# Diff-Probe-Supply.net
KiCad netlist of a schematic drawn in Altium Designer
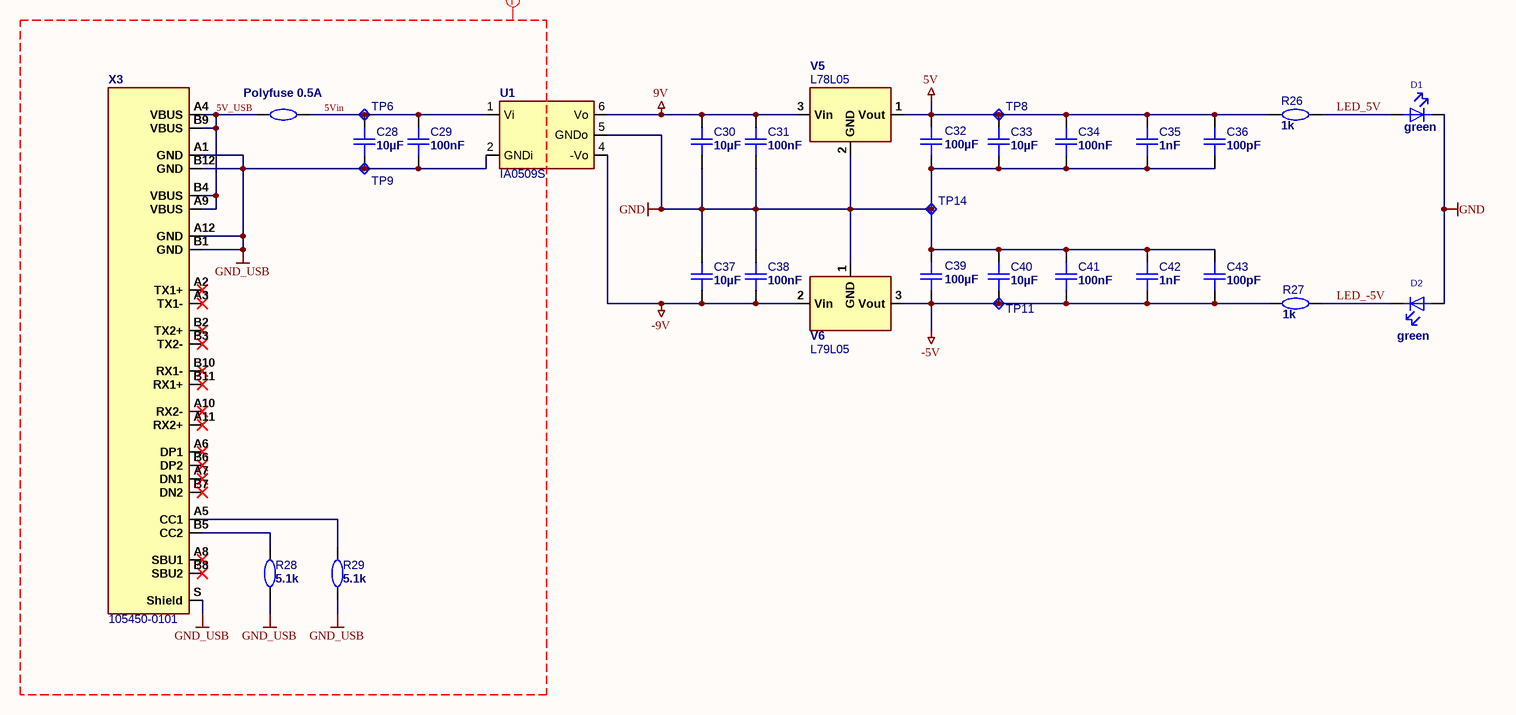
[diagram p0: Diff-Probe-Supply.SchDoc]

(export (version "E")
  (design (tool "Eeschema 10.0.6"))
  (components
    (comp (ref "C28")
      (value "10µF")
      (footprint "C-0805_2012_155_L_RF")
      (description "Cap Cer SMD 10u 6.3V 10% 0805 X7R")
      (fields
        (field (name "MANUFACTURER") "MURATA")
        (field (name "MANUFACTURER PART NUMBER") "GCM21BR70J106KE22")
        (field (name "USER") "zupa")
      )
      (libsource (lib "GPV Switzerland SA") (part "CAP"))
    )
    (comp (ref "C29")
      (value "100nF")
      (footprint "C-0603_1608_095_L_RF")
      (description "Cap Cer SMD 100n 100V 10% 0603 X7R")
      (fields
        (field (name "MANUFACTURER PART NUMBER") "GRM188R72A104KA35")
        (field (name "MANUFACTURER") "MURATA")
        (field (name "USER") "zupa")
      )
      (libsource (lib "GPV Switzerland SA") (part "CAP"))
    )
    (comp (ref "C30")
      (value "10µF")
      (footprint "C-0805_2012_155_L_RF")
      (description "Cap Cer SMD 10u 6.3V 10% 0805 X7R")
      (fields
        (field (name "MANUFACTURER") "MURATA")
        (field (name "MANUFACTURER PART NUMBER") "GCM21BR70J106KE22")
        (field (name "USER") "zupa")
      )
      (libsource (lib "GPV Switzerland SA") (part "CAP"))
    )
    (comp (ref "C31")
      (value "100nF")
      (footprint "C-0603_1608_095_L_RF")
      (description "Cap Cer SMD 100n 100V 10% 0603 X7R")
      (fields
        (field (name "MANUFACTURER PART NUMBER") "GRM188R72A104KA35")
        (field (name "MANUFACTURER") "MURATA")
        (field (name "USER") "zupa")
      )
      (libsource (lib "GPV Switzerland SA") (part "CAP"))
    )
    (comp (ref "C32")
      (value "100µF")
      (footprint "C-1206_3216_180_L_RF")
      (description "Cap Cer SMD 100u 6.3V 20% 1206 X5R")
      (fields
        (field (name "MANUFACTURER") "AVX")
        (field (name "MANUFACTURER PART NUMBER") "12066D107MAT2A")
        (field (name "USER") "balu")
      )
      (libsource (lib "GPV Switzerland SA") (part "CAP"))
    )
    (comp (ref "C33")
      (value "10µF")
      (footprint "C-0805_2012_155_L_RF")
      (description "Cap Cer SMD 10u 6.3V 10% 0805 X7R")
      (fields
        (field (name "MANUFACTURER") "MURATA")
        (field (name "MANUFACTURER PART NUMBER") "GCM21BR70J106KE22")
        (field (name "USER") "zupa")
      )
      (libsource (lib "GPV Switzerland SA") (part "CAP"))
    )
    (comp (ref "C34")
      (value "100nF")
      (footprint "C-0603_1608_095_L_RF")
      (description "Cap Cer SMD 100n 100V 10% 0603 X7R")
      (fields
        (field (name "MANUFACTURER PART NUMBER") "GRM188R72A104KA35")
        (field (name "MANUFACTURER") "MURATA")
        (field (name "USER") "zupa")
      )
      (libsource (lib "GPV Switzerland SA") (part "CAP"))
    )
    (comp (ref "C35")
      (value "1nF")
      (footprint "C-0603_1608_100_L_RF")
      (description "Cap Cer SMD 1n 50V 1% 0603 C0G")
      (fields
        (field (name "MANUFACTURER PART NUMBER") "06035A102FAT*")
        (field (name "MANUFACTURER") "AVX")
        (field (name "USER") "zupa")
      )
      (libsource (lib "GPV Switzerland SA") (part "CAP"))
    )
    (comp (ref "C36")
      (value "100pF")
      (footprint "C-0603_1608_095_L_RF")
      (description "Cap Cer SMD 100p 50V 5% 0603 C0G")
      (fields
        (field (name "MANUFACTURER PART NUMBER") "CC0603J*NPO9BN101")
        (field (name "MANUFACTURER") "YAGEO")
        (field (name "USER") "zupa")
      )
      (libsource (lib "GPV Switzerland SA") (part "CAP"))
    )
    (comp (ref "C37")
      (value "10µF")
      (footprint "C-0805_2012_155_L_RF")
      (description "Cap Cer SMD 10u 6.3V 10% 0805 X7R")
      (fields
        (field (name "MANUFACTURER") "MURATA")
        (field (name "MANUFACTURER PART NUMBER") "GCM21BR70J106KE22")
        (field (name "USER") "zupa")
      )
      (libsource (lib "GPV Switzerland SA") (part "CAP"))
    )
    (comp (ref "C38")
      (value "100nF")
      (footprint "C-0603_1608_095_L_RF")
      (description "Cap Cer SMD 100n 100V 10% 0603 X7R")
      (fields
        (field (name "MANUFACTURER PART NUMBER") "GRM188R72A104KA35")
        (field (name "MANUFACTURER") "MURATA")
        (field (name "USER") "zupa")
      )
      (libsource (lib "GPV Switzerland SA") (part "CAP"))
    )
    (comp (ref "C39")
      (value "100µF")
      (footprint "C-1206_3216_180_L_RF")
      (description "Cap Cer SMD 100u 6.3V 20% 1206 X5R")
      (fields
        (field (name "MANUFACTURER") "AVX")
        (field (name "MANUFACTURER PART NUMBER") "12066D107MAT2A")
        (field (name "USER") "balu")
      )
      (libsource (lib "GPV Switzerland SA") (part "CAP"))
    )
    (comp (ref "C40")
      (value "10µF")
      (footprint "C-0805_2012_155_L_RF")
      (description "Cap Cer SMD 10u 6.3V 10% 0805 X7R")
      (fields
        (field (name "MANUFACTURER") "MURATA")
        (field (name "MANUFACTURER PART NUMBER") "GCM21BR70J106KE22")
        (field (name "USER") "zupa")
      )
      (libsource (lib "GPV Switzerland SA") (part "CAP"))
    )
    (comp (ref "C41")
      (value "100nF")
      (footprint "C-0603_1608_095_L_RF")
      (description "Cap Cer SMD 100n 100V 10% 0603 X7R")
      (fields
        (field (name "MANUFACTURER PART NUMBER") "GRM188R72A104KA35")
        (field (name "MANUFACTURER") "MURATA")
        (field (name "USER") "zupa")
      )
      (libsource (lib "GPV Switzerland SA") (part "CAP"))
    )
    (comp (ref "C42")
      (value "1nF")
      (footprint "C-0603_1608_100_L_RF")
      (description "Cap Cer SMD 1n 50V 1% 0603 C0G")
      (fields
        (field (name "MANUFACTURER PART NUMBER") "06035A102FAT*")
        (field (name "MANUFACTURER") "AVX")
        (field (name "USER") "zupa")
      )
      (libsource (lib "GPV Switzerland SA") (part "CAP"))
    )
    (comp (ref "C43")
      (value "100pF")
      (footprint "C-0603_1608_095_L_RF")
      (description "Cap Cer SMD 100p 50V 5% 0603 C0G")
      (fields
        (field (name "MANUFACTURER PART NUMBER") "CC0603J*NPO9BN101")
        (field (name "MANUFACTURER") "YAGEO")
        (field (name "USER") "zupa")
      )
      (libsource (lib "GPV Switzerland SA") (part "CAP"))
    )
    (comp (ref "D1")
      (value "green")
      (footprint "LED-0603_1608_Green_L_RF")
      (description "LED Green LTST-C190KGKT 0603")
      (fields
        (field (name "MANUFACTURER") "Lite-On Inc")
        (field (name "MANUFACTURER PART NUMBER") "LTST-C190KGKT")
        (field (name "USER") "epph")
      )
      (libsource (lib "GPV Switzerland SA") (part "LED"))
    )
    (comp (ref "D2")
      (value "green")
      (footprint "LED-0603_1608_Green_L_RF")
      (description "LED Green LTST-C190KGKT 0603")
      (fields
        (field (name "MANUFACTURER") "Lite-On Inc")
        (field (name "MANUFACTURER PART NUMBER") "LTST-C190KGKT")
        (field (name "USER") "epph")
      )
      (libsource (lib "GPV Switzerland SA") (part "LED"))
    )
    (comp (ref "R25")
      (value "Res 0R 0805")
      (footprint "R-0805_2012_060_L_RF")
      (description "Res SMD 0R 1% 0.125W 0805")
      (fields
        (field (name "MANUFACTURER PART NUMBER") "RC0805JR-070RL")
        (field (name "MANUFACTURER") "YAGEO")
        (field (name "USER") "zupa")
      )
      (libsource (lib "GPV Switzerland SA") (part "RES"))
    )
    (comp (ref "R26")
      (value "1k")
      (footprint "R-0603_1608_050_L_RF")
      (description "Res SMD 1k 1% 0.1W 0603")
      (fields
        (field (name "MANUFACTURER") "YAGEO")
        (field (name "MANUFACTURER PART NUMBER") "RC0603FR-071KL")
        (field (name "USER") "zupa")
      )
      (libsource (lib "GPV Switzerland SA") (part "RES"))
    )
    (comp (ref "R27")
      (value "1k")
      (footprint "R-0603_1608_050_L_RF")
      (description "Res SMD 1k 1% 0.1W 0603")
      (fields
        (field (name "MANUFACTURER") "YAGEO")
        (field (name "MANUFACTURER PART NUMBER") "RC0603FR-071KL")
        (field (name "USER") "zupa")
      )
      (libsource (lib "GPV Switzerland SA") (part "RES"))
    )
    (comp (ref "R28")
      (value "5.1k")
      (footprint "R-0603_1608_050_L_RF")
      (description "Res SMD 5k1 1% 0.1W 0603")
      (fields
        (field (name "MANUFACTURER PART NUMBER") "RC0603FR-075K1L")
        (field (name "MANUFACTURER") "YAGEO")
        (field (name "USER") "napa")
      )
      (libsource (lib "GPV Switzerland SA") (part "RES"))
    )
    (comp (ref "R29")
      (value "5.1k")
      (footprint "R-0603_1608_050_L_RF")
      (description "Res SMD 5k1 1% 0.1W 0603")
      (fields
        (field (name "MANUFACTURER PART NUMBER") "RC0603FR-075K1L")
        (field (name "MANUFACTURER") "YAGEO")
        (field (name "USER") "napa")
      )
      (libsource (lib "GPV Switzerland SA") (part "RES"))
    )
    (comp (ref "TP6")
      (value "TestPoint 1.6mm with via")
      (footprint "TP_1.6mm_via")
      (description "TestPoint 1.6mm with via v70h30")
      (fields (field (name "USER") "epph"))
      (libsource (lib "GPV Switzerland SA") (part "Testpoint"))
    )
    (comp (ref "TP8")
      (value "TestPoint 1.6mm with via")
      (footprint "TP_1.6mm_via")
      (description "TestPoint 1.6mm with via v70h30")
      (fields (field (name "USER") "epph"))
      (libsource (lib "GPV Switzerland SA") (part "Testpoint"))
    )
    (comp (ref "TP9")
      (value "TestPoint 1.6mm with via")
      (footprint "TP_1.6mm_via")
      (description "TestPoint 1.6mm with via v70h30")
      (fields (field (name "USER") "epph"))
      (libsource (lib "GPV Switzerland SA") (part "Testpoint"))
    )
    (comp (ref "TP11")
      (value "TestPoint 1.6mm with via")
      (footprint "TP_1.6mm_via")
      (description "TestPoint 1.6mm with via v70h30")
      (fields (field (name "USER") "epph"))
      (libsource (lib "GPV Switzerland SA") (part "Testpoint"))
    )
    (comp (ref "TP14")
      (value "TestPoint 1.6mm with via")
      (footprint "TP_1.6mm_via")
      (description "TestPoint 1.6mm with via v70h30")
      (fields (field (name "USER") "epph"))
      (libsource (lib "GPV Switzerland SA") (part "Testpoint"))
    )
    (comp (ref "U1")
      (value "IA0509S")
      (footprint "SIP7")
      (description "IC DC/DC Converter 5VIN +-9VOUT 1W")
      (fields (field (name "MANUFACTURER") "XP Power"))
      (libsource (lib "Global Library") (part "IA0509S"))
    )
    (comp (ref "V5")
      (value "L78L05")
      (footprint "SOT-89-3")
      (description "IC REG 5V SOT-89-3")
      (fields (field (name "MANUFACTURER") "ST"))
      (libsource (lib "Global Library") (part "L78L05"))
    )
    (comp (ref "V6")
      (value "L79L05")
      (footprint "SOT-89-3")
      (description "IC REG -5V SOT-89-3")
      (fields (field (name "MANUFACTURER") "ST"))
      (libsource (lib "Global Library") (part "L79L05"))
    )
    (comp (ref "X3")
      (value "105450-0101")
      (footprint "105450-0101")
      (description "CONN USB-C 16pin")
      (fields (field (name "MANUFACTURER") "Molex"))
      (libsource (lib "Global Library") (part "105450-0101"))
    )
  )
  (nets
    (net (code "1") (name "-5V") (class "Default")
      (node (ref "C39") (pin "2") (pinfunction "2_2") (pintype "passive"))
      (node (ref "C40") (pin "1") (pinfunction "1_1") (pintype "passive"))
      (node (ref "C41") (pin "1") (pinfunction "1_1") (pintype "passive"))
      (node (ref "C42") (pin "1") (pinfunction "1_1") (pintype "passive"))
      (node (ref "C43") (pin "1") (pinfunction "1_1") (pintype "passive"))
      (node (ref "R27") (pin "1") (pinfunction "1_1") (pintype "passive"))
      (node (ref "TP11") (pin "1") (pinfunction "1_1") (pintype "passive"))
      (node (ref "V6") (pin "3") (pinfunction "Vout_3") (pintype "passive"))
    )
    (net (code "2") (name "-9V") (class "Default")
      (node (ref "C37") (pin "1") (pinfunction "1_1") (pintype "passive"))
      (node (ref "C38") (pin "1") (pinfunction "1_1") (pintype "passive"))
      (node (ref "U1") (pin "4") (pinfunction "-Vo_4") (pintype "passive"))
      (node (ref "V6") (pin "2") (pinfunction "Vin_2") (pintype "passive"))
    )
    (net (code "3") (name "/5V_USB") (class "Default")
      (node (ref "R25") (pin "1") (pinfunction "1_1") (pintype "passive"))
      (node (ref "X3") (pin "A4") (pinfunction "VBUS_A4") (pintype "passive"))
      (node (ref "X3") (pin "A9") (pinfunction "VBUS_A9") (pintype "passive"))
      (node (ref "X3") (pin "B4") (pinfunction "VBUS_B4") (pintype "passive"))
      (node (ref "X3") (pin "B9") (pinfunction "VBUS_B9") (pintype "passive"))
    )
    (net (code "4") (name "/5Vin") (class "Default")
      (node (ref "C28") (pin "2") (pinfunction "2_2") (pintype "passive"))
      (node (ref "C29") (pin "2") (pinfunction "2_2") (pintype "passive"))
      (node (ref "R25") (pin "2") (pinfunction "2_2") (pintype "passive"))
      (node (ref "TP6") (pin "1") (pinfunction "1_1") (pintype "passive"))
      (node (ref "U1") (pin "1") (pinfunction "Vi_1") (pintype "passive"))
    )
    (net (code "5") (name "/LED_-5V") (class "Default")
      (node (ref "D2") (pin "2") (pinfunction "2_2") (pintype "passive"))
      (node (ref "R27") (pin "2") (pinfunction "2_2") (pintype "passive"))
    )
    (net (code "6") (name "/LED_5V") (class "Default")
      (node (ref "D1") (pin "1") (pinfunction "1_1") (pintype "passive"))
      (node (ref "R26") (pin "1") (pinfunction "1_1") (pintype "passive"))
    )
    (net (code "7") (name "5V") (class "Default")
      (node (ref "C32") (pin "1") (pinfunction "1_1") (pintype "passive"))
      (node (ref "C33") (pin "2") (pinfunction "2_2") (pintype "passive"))
      (node (ref "C34") (pin "2") (pinfunction "2_2") (pintype "passive"))
      (node (ref "C35") (pin "2") (pinfunction "2_2") (pintype "passive"))
      (node (ref "C36") (pin "2") (pinfunction "2_2") (pintype "passive"))
      (node (ref "R26") (pin "2") (pinfunction "2_2") (pintype "passive"))
      (node (ref "TP8") (pin "1") (pinfunction "1_1") (pintype "passive"))
      (node (ref "V5") (pin "1") (pinfunction "Vout_1") (pintype "passive"))
    )
    (net (code "8") (name "9V") (class "Default")
      (node (ref "C30") (pin "2") (pinfunction "2_2") (pintype "passive"))
      (node (ref "C31") (pin "2") (pinfunction "2_2") (pintype "passive"))
      (node (ref "U1") (pin "6") (pinfunction "Vo_6") (pintype "passive"))
      (node (ref "V5") (pin "3") (pinfunction "Vin_3") (pintype "passive"))
    )
    (net (code "9") (name "GND") (class "Default")
      (node (ref "C30") (pin "1") (pinfunction "1_1") (pintype "passive"))
      (node (ref "C31") (pin "1") (pinfunction "1_1") (pintype "passive"))
      (node (ref "C32") (pin "2") (pinfunction "2_2") (pintype "passive"))
      (node (ref "C33") (pin "1") (pinfunction "1_1") (pintype "passive"))
      (node (ref "C34") (pin "1") (pinfunction "1_1") (pintype "passive"))
      (node (ref "C35") (pin "1") (pinfunction "1_1") (pintype "passive"))
      (node (ref "C36") (pin "1") (pinfunction "1_1") (pintype "passive"))
      (node (ref "C37") (pin "2") (pinfunction "2_2") (pintype "passive"))
      (node (ref "C38") (pin "2") (pinfunction "2_2") (pintype "passive"))
      (node (ref "C39") (pin "1") (pinfunction "1_1") (pintype "passive"))
      (node (ref "C40") (pin "2") (pinfunction "2_2") (pintype "passive"))
      (node (ref "C41") (pin "2") (pinfunction "2_2") (pintype "passive"))
      (node (ref "C42") (pin "2") (pinfunction "2_2") (pintype "passive"))
      (node (ref "C43") (pin "2") (pinfunction "2_2") (pintype "passive"))
      (node (ref "D1") (pin "2") (pinfunction "2_2") (pintype "passive"))
      (node (ref "D2") (pin "1") (pinfunction "1_1") (pintype "passive"))
      (node (ref "TP14") (pin "1") (pinfunction "1_1") (pintype "passive"))
      (node (ref "U1") (pin "5") (pinfunction "GNDo_5") (pintype "passive"))
      (node (ref "V5") (pin "2") (pinfunction "GND_2") (pintype "passive"))
      (node (ref "V6") (pin "1") (pinfunction "GND_1") (pintype "passive"))
    )
    (net (code "10") (name "GND_USB") (class "Default")
      (node (ref "C28") (pin "1") (pinfunction "1_1") (pintype "passive"))
      (node (ref "C29") (pin "1") (pinfunction "1_1") (pintype "passive"))
      (node (ref "R28") (pin "1") (pinfunction "1_1") (pintype "passive"))
      (node (ref "R29") (pin "1") (pinfunction "1_1") (pintype "passive"))
      (node (ref "TP9") (pin "1") (pinfunction "1_1") (pintype "passive"))
      (node (ref "U1") (pin "2") (pinfunction "GNDi_2") (pintype "passive"))
      (node (ref "X3") (pin "A1") (pinfunction "GND_A1") (pintype "passive"))
      (node (ref "X3") (pin "A12") (pinfunction "GND_A12") (pintype "passive"))
      (node (ref "X3") (pin "B1") (pinfunction "GND_B1") (pintype "passive"))
      (node (ref "X3") (pin "B12") (pinfunction "GND_B12") (pintype "passive"))
      (node (ref "X3") (pin "S") (pinfunction "Shield_S") (pintype "passive"))
    )
    (net (code "11") (name "Net-(X3-CC1)") (class "Default")
      (node (ref "R29") (pin "2") (pinfunction "2_2") (pintype "passive"))
      (node (ref "X3") (pin "A5") (pinfunction "CC1_A5") (pintype "passive"))
    )
    (net (code "12") (name "Net-(X3-CC2)") (class "Default")
      (node (ref "R28") (pin "2") (pinfunction "2_2") (pintype "passive"))
      (node (ref "X3") (pin "B5") (pinfunction "CC2_B5") (pintype "passive"))
    )
    (net (code "13") (name "unconnected-(X3-DN1-PadA7)") (class "Default")
      (node (ref "X3") (pin "A7") (pinfunction "DN1_A7") (pintype "passive+no_connect"))
    )
    (net (code "14") (name "unconnected-(X3-DN2-PadB7)") (class "Default")
      (node (ref "X3") (pin "B7") (pinfunction "DN2_B7") (pintype "passive+no_connect"))
    )
    (net (code "15") (name "unconnected-(X3-DP1-PadA6)") (class "Default")
      (node (ref "X3") (pin "A6") (pinfunction "DP1_A6") (pintype "passive+no_connect"))
    )
    (net (code "16") (name "unconnected-(X3-DP2-PadB6)") (class "Default")
      (node (ref "X3") (pin "B6") (pinfunction "DP2_B6") (pintype "passive+no_connect"))
    )
    (net (code "17") (name "unconnected-(X3-RX1+-PadB11)") (class "Default")
      (node (ref "X3") (pin "B11") (pinfunction "RX1+_B11") (pintype "passive+no_connect"))
    )
    (net (code "18") (name "unconnected-(X3-RX1--PadB10)") (class "Default")
      (node (ref "X3") (pin "B10") (pinfunction "RX1-_B10") (pintype "passive+no_connect"))
    )
    (net (code "19") (name "unconnected-(X3-RX2+-PadA11)") (class "Default")
      (node (ref "X3") (pin "A11") (pinfunction "RX2+_A11") (pintype "passive+no_connect"))
    )
    (net (code "20") (name "unconnected-(X3-RX2--PadA10)") (class "Default")
      (node (ref "X3") (pin "A10") (pinfunction "RX2-_A10") (pintype "passive+no_connect"))
    )
    (net (code "21") (name "unconnected-(X3-SBU1-PadA8)") (class "Default")
      (node (ref "X3") (pin "A8") (pinfunction "SBU1_A8") (pintype "passive+no_connect"))
    )
    (net (code "22") (name "unconnected-(X3-SBU2-PadB8)") (class "Default")
      (node (ref "X3") (pin "B8") (pinfunction "SBU2_B8") (pintype "passive+no_connect"))
    )
    (net (code "23") (name "unconnected-(X3-TX1+-PadA2)") (class "Default")
      (node (ref "X3") (pin "A2") (pinfunction "TX1+_A2") (pintype "passive+no_connect"))
    )
    (net (code "24") (name "unconnected-(X3-TX1--PadA3)") (class "Default")
      (node (ref "X3") (pin "A3") (pinfunction "TX1-_A3") (pintype "passive+no_connect"))
    )
    (net (code "25") (name "unconnected-(X3-TX2+-PadB2)") (class "Default")
      (node (ref "X3") (pin "B2") (pinfunction "TX2+_B2") (pintype "passive+no_connect"))
    )
    (net (code "26") (name "unconnected-(X3-TX2--PadB3)") (class "Default")
      (node (ref "X3") (pin "B3") (pinfunction "TX2-_B3") (pintype "passive+no_connect"))
    )
  )
)
